# SCH_555-chaser_2025-11-02.net
KiCad netlist of a schematic drawn in EasyEDA
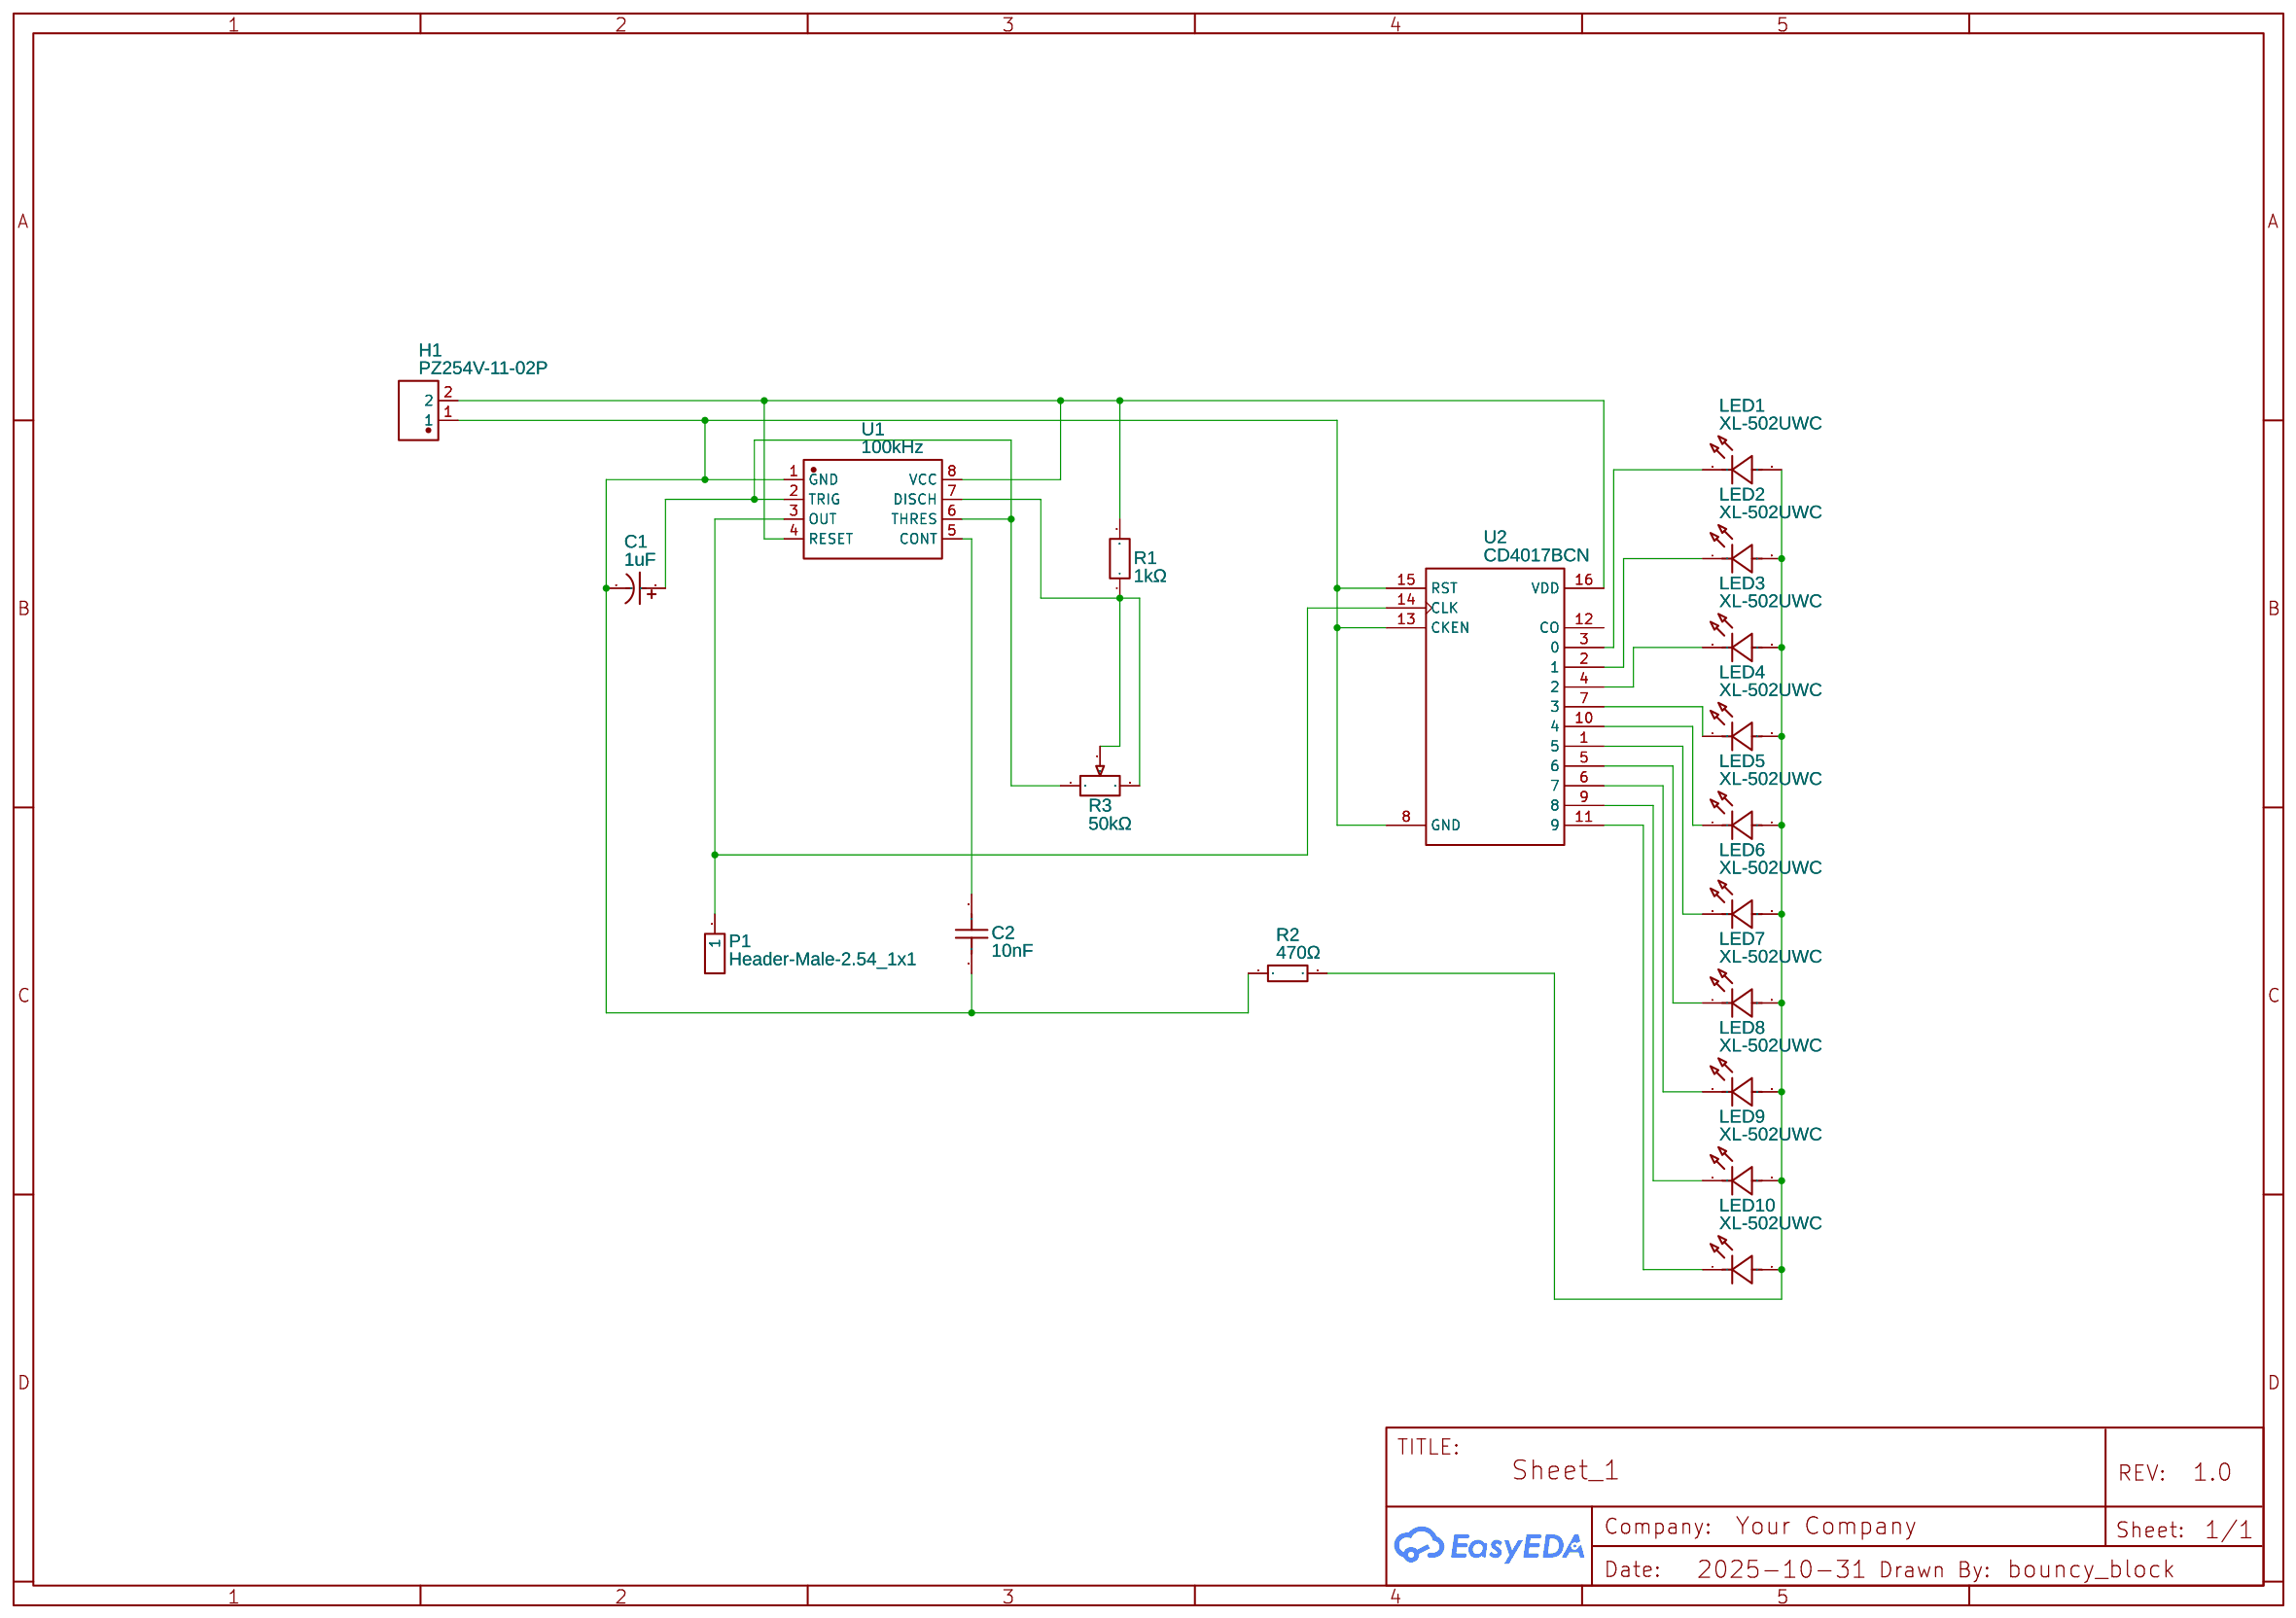
[diagram p0: schematic sheet]

(export (version "E")
  (design (tool "Eeschema 10.0.6"))
  (components
    (comp (ref "C1")
      (value "1uF")
      (fields (field (name "Manufacturer Part") "KF010M050C110A") (field (name "Manufacturer") "CapXon(丰宾)"))
      (libsource (lib "") (part "KF010M050C110A"))
    )
    (comp (ref "C2")
      (value "10nF")
      (fields (field (name "Manufacturer Part") "N09F1B103MN0B0S0N0") (field (name "Manufacturer") "STE(松田)"))
      (libsource (lib "") (part "N09F1B103MN0B0S0N0"))
    )
    (comp (ref "H1")
      (value "PZ254V-11-02P")
      (fields (field (name "Manufacturer") "XFCN(兴飞)"))
      (libsource (lib "") (part "PZ254V-11-02P"))
    )
    (comp (ref "LED1")
      (value "XL-502UWC")
      (fields (field (name "Manufacturer") "XINGLIGHT(成兴光)"))
      (libsource (lib "") (part "XL-502UWC"))
    )
    (comp (ref "LED2")
      (value "XL-502UWC")
      (fields (field (name "Manufacturer") "XINGLIGHT(成兴光)"))
      (libsource (lib "") (part "XL-502UWC"))
    )
    (comp (ref "LED3")
      (value "XL-502UWC")
      (fields (field (name "Manufacturer") "XINGLIGHT(成兴光)"))
      (libsource (lib "") (part "XL-502UWC"))
    )
    (comp (ref "LED4")
      (value "XL-502UWC")
      (fields (field (name "Manufacturer") "XINGLIGHT(成兴光)"))
      (libsource (lib "") (part "XL-502UWC"))
    )
    (comp (ref "LED5")
      (value "XL-502UWC")
      (fields (field (name "Manufacturer") "XINGLIGHT(成兴光)"))
      (libsource (lib "") (part "XL-502UWC"))
    )
    (comp (ref "LED6")
      (value "XL-502UWC")
      (fields (field (name "Manufacturer") "XINGLIGHT(成兴光)"))
      (libsource (lib "") (part "XL-502UWC"))
    )
    (comp (ref "LED7")
      (value "XL-502UWC")
      (fields (field (name "Manufacturer") "XINGLIGHT(成兴光)"))
      (libsource (lib "") (part "XL-502UWC"))
    )
    (comp (ref "LED8")
      (value "XL-502UWC")
      (fields (field (name "Manufacturer") "XINGLIGHT(成兴光)"))
      (libsource (lib "") (part "XL-502UWC"))
    )
    (comp (ref "LED9")
      (value "XL-502UWC")
      (fields (field (name "Manufacturer") "XINGLIGHT(成兴光)"))
      (libsource (lib "") (part "XL-502UWC"))
    )
    (comp (ref "LED10")
      (value "XL-502UWC")
      (fields (field (name "Manufacturer") "XINGLIGHT(成兴光)"))
      (libsource (lib "") (part "XL-502UWC"))
    )
    (comp (ref "P1")
      (value "Header-Male-2.54_1x1")
      (fields (field (name "Manufacturer Part") "2.54-1*1P针") (field (name "Manufacturer") "BOOMELE(博穆精密)"))
      (libsource (lib "") (part "Header-Male-2.54_1x1"))
    )
    (comp (ref "R1")
      (value "1kΩ")
      (fields (field (name "Manufacturer Part") "MF1/4W-1KΩ±1%T52") (field (name "Manufacturer") "华星机电"))
      (libsource (lib "") (part "MF1/4W-1KΩ±1%T52"))
    )
    (comp (ref "R2")
      (value "470Ω")
      (fields
        (field (name "Manufacturer Part") "MFR0W4F4700A50")
        (field (name "Manufacturer") "UNI-ROYAL(厚声)")
      )
      (libsource (lib "") (part "MFR0W4F4700A50"))
    )
    (comp (ref "R3")
      (value "50kΩ")
      (fields (field (name "Manufacturer Part") "3296X-1-503") (field (name "Manufacturer") "BOCHEN(博晨)"))
      (libsource (lib "") (part "3296X-1-503_C118912"))
    )
    (comp (ref "U1")
      (value "100kHz")
      (fields (field (name "Manufacturer Part") "NE555P") (field (name "Manufacturer") "TI(德州仪器)"))
      (libsource (lib "") (part "NE555P"))
    )
    (comp (ref "U2") (value "CD4017BCN") (libsource (lib "") (part "CD4017BCN")))
  )
  (nets
    (net (code "1") (name "Net-(LED1-A)") (class "Default")
      (node (ref "LED1") (pin "2") (pinfunction "A_2") (pintype "unspecified"))
      (node (ref "LED10") (pin "2") (pinfunction "A_2") (pintype "unspecified"))
      (node (ref "LED2") (pin "2") (pinfunction "A_2") (pintype "unspecified"))
      (node (ref "LED3") (pin "2") (pinfunction "A_2") (pintype "unspecified"))
      (node (ref "LED4") (pin "2") (pinfunction "A_2") (pintype "unspecified"))
      (node (ref "LED5") (pin "2") (pinfunction "A_2") (pintype "unspecified"))
      (node (ref "LED6") (pin "2") (pinfunction "A_2") (pintype "unspecified"))
      (node (ref "LED7") (pin "2") (pinfunction "A_2") (pintype "unspecified"))
      (node (ref "LED8") (pin "2") (pinfunction "A_2") (pintype "unspecified"))
      (node (ref "LED9") (pin "2") (pinfunction "A_2") (pintype "unspecified"))
      (node (ref "R2") (pin "2") (pinfunction "2_2") (pintype "input"))
    )
    (net (code "2") (name "Net-(LED1-K)") (class "Default")
      (node (ref "LED1") (pin "1") (pinfunction "K_1") (pintype "unspecified"))
      (node (ref "U2") (pin "3") (pinfunction "0_3") (pintype "output"))
    )
    (net (code "3") (name "Net-(LED2-K)") (class "Default")
      (node (ref "LED2") (pin "1") (pinfunction "K_1") (pintype "unspecified"))
      (node (ref "U2") (pin "2") (pinfunction "1_2") (pintype "output"))
    )
    (net (code "4") (name "Net-(LED3-K)") (class "Default")
      (node (ref "LED3") (pin "1") (pinfunction "K_1") (pintype "unspecified"))
      (node (ref "U2") (pin "4") (pinfunction "2_4") (pintype "output"))
    )
    (net (code "5") (name "Net-(LED4-K)") (class "Default")
      (node (ref "LED4") (pin "1") (pinfunction "K_1") (pintype "unspecified"))
      (node (ref "U2") (pin "7") (pinfunction "3_7") (pintype "output"))
    )
    (net (code "6") (name "Net-(LED5-K)") (class "Default")
      (node (ref "LED5") (pin "1") (pinfunction "K_1") (pintype "unspecified"))
      (node (ref "U2") (pin "10") (pinfunction "4_10") (pintype "output"))
    )
    (net (code "7") (name "Net-(LED6-K)") (class "Default")
      (node (ref "LED6") (pin "1") (pinfunction "K_1") (pintype "unspecified"))
      (node (ref "U2") (pin "1") (pinfunction "5_1") (pintype "output"))
    )
    (net (code "8") (name "Net-(LED7-K)") (class "Default")
      (node (ref "LED7") (pin "1") (pinfunction "K_1") (pintype "unspecified"))
      (node (ref "U2") (pin "5") (pinfunction "6_5") (pintype "output"))
    )
    (net (code "9") (name "Net-(LED8-K)") (class "Default")
      (node (ref "LED8") (pin "1") (pinfunction "K_1") (pintype "unspecified"))
      (node (ref "U2") (pin "6") (pinfunction "7_6") (pintype "output"))
    )
    (net (code "10") (name "Net-(LED9-K)") (class "Default")
      (node (ref "LED9") (pin "1") (pinfunction "K_1") (pintype "unspecified"))
      (node (ref "U2") (pin "9") (pinfunction "8_9") (pintype "output"))
    )
    (net (code "11") (name "Net-(LED10-K)") (class "Default")
      (node (ref "LED10") (pin "1") (pinfunction "K_1") (pintype "unspecified"))
      (node (ref "U2") (pin "11") (pinfunction "9_11") (pintype "output"))
    )
    (net (code "12") (name "Net-(U1-CONT)") (class "Default")
      (node (ref "C2") (pin "2") (pinfunction "2_2") (pintype "unspecified"))
      (node (ref "U1") (pin "5") (pinfunction "CONT_5") (pintype "unspecified"))
    )
    (net (code "13") (name "Net-(U1-DISCH)") (class "Default")
      (node (ref "R1") (pin "1") (pinfunction "1_1") (pintype "unspecified"))
      (node (ref "R3") (pin "2") (pinfunction "2_2") (pintype "input"))
      (node (ref "R3") (pin "3") (pinfunction "3_3") (pintype "input"))
      (node (ref "U1") (pin "7") (pinfunction "DISCH_7") (pintype "unspecified"))
    )
    (net (code "14") (name "Net-(U1-GND)") (class "Default")
      (node (ref "C1") (pin "2") (pinfunction "2_2") (pintype "input"))
      (node (ref "C2") (pin "1") (pinfunction "1_1") (pintype "unspecified"))
      (node (ref "H1") (pin "1") (pinfunction "1_1") (pintype "unspecified"))
      (node (ref "R2") (pin "1") (pinfunction "1_1") (pintype "input"))
      (node (ref "U1") (pin "1") (pinfunction "GND_1") (pintype "unspecified"))
      (node (ref "U2") (pin "13") (pinfunction "CKEN_13") (pintype "unspecified"))
      (node (ref "U2") (pin "15") (pinfunction "RST_15") (pintype "unspecified"))
      (node (ref "U2") (pin "8") (pinfunction "GND_8") (pintype "passive"))
    )
    (net (code "15") (name "Net-(U1-OUT)") (class "Default")
      (node (ref "P1") (pin "1") (pinfunction "1_1") (pintype "input"))
      (node (ref "U1") (pin "3") (pinfunction "OUT_3") (pintype "unspecified"))
      (node (ref "U2") (pin "14") (pinfunction "CLK_14") (pintype "unspecified"))
    )
    (net (code "16") (name "Net-(U1-RESET)") (class "Default")
      (node (ref "H1") (pin "2") (pinfunction "2_2") (pintype "unspecified"))
      (node (ref "R1") (pin "2") (pinfunction "2_2") (pintype "unspecified"))
      (node (ref "U1") (pin "4") (pinfunction "RESET_4") (pintype "unspecified"))
      (node (ref "U1") (pin "8") (pinfunction "VCC_8") (pintype "unspecified"))
      (node (ref "U2") (pin "16") (pinfunction "VDD_16") (pintype "passive"))
    )
    (net (code "17") (name "Net-(U1-THRES)") (class "Default")
      (node (ref "C1") (pin "1") (pinfunction "1_1") (pintype "input"))
      (node (ref "R3") (pin "1") (pinfunction "1_1") (pintype "input"))
      (node (ref "U1") (pin "2") (pinfunction "TRIG_2") (pintype "unspecified"))
      (node (ref "U1") (pin "6") (pinfunction "THRES_6") (pintype "unspecified"))
    )
    (net (code "18") (name "unconnected-(U2-CO-Pad12)") (class "Default")
      (node (ref "U2") (pin "12") (pinfunction "CO_12") (pintype "output"))
    )
  )
)
